# BatteryManagement.net
KiCad netlist of a schematic drawn in Altium Designer
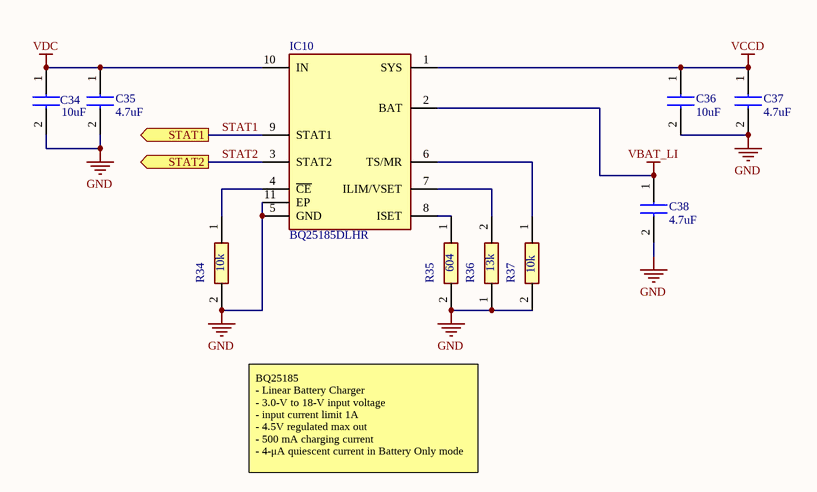
[diagram p0: BatteryManagement.SchDoc]

(export (version "E")
  (design (tool "Eeschema 10.0.6"))
  (components
    (comp (ref "C34")
      (value "10uF")
      (footprint "SamacSys:GRM18x")
      (description "Capacitor")
      (fields
        (field (name "MANUFACTURER_PART_NUMBER") "GRM188R61E106KA73D")
        (field (name "MOUSER PART NUMBER") "81-GRM188R61E106KA3D")
      )
      (libsource (lib "*") (part "GRM188R61E106KA73D"))
    )
    (comp (ref "C35")
      (value "4.7uF")
      (footprint "SamacSys:CAPC1608X90N")
      (description "Capacitor")
      (fields
        (field (name "MANUFACTURER_PART_NUMBER") "GRM188R61E475KE11J")
        (field (name "MOUSER PART NUMBER") "81-GRM188R61E475KE1J")
      )
      (libsource (lib "*") (part "GRM188R61E475KE11J"))
    )
    (comp (ref "C36")
      (value "10uF")
      (footprint "SamacSys:GRM18x")
      (description "Capacitor")
      (fields
        (field (name "MANUFACTURER_PART_NUMBER") "GRM188R61E106KA73D")
        (field (name "MOUSER PART NUMBER") "81-GRM188R61E106KA3D")
      )
      (libsource (lib "*") (part "GRM188R61E106KA73D"))
    )
    (comp (ref "C37")
      (value "4.7uF")
      (footprint "SamacSys:CAPC1608X90N")
      (description "Capacitor")
      (fields
        (field (name "MANUFACTURER_PART_NUMBER") "GRM188R61E475KE11J")
        (field (name "MOUSER PART NUMBER") "81-GRM188R61E475KE1J")
      )
      (libsource (lib "*") (part "GRM188R61E475KE11J"))
    )
    (comp (ref "C38")
      (value "4.7uF")
      (footprint "SamacSys:CAPC1608X90N")
      (description "Capacitor")
      (fields
        (field (name "MANUFACTURER_PART_NUMBER") "GRM188R61E475KE11J")
        (field (name "MOUSER PART NUMBER") "81-GRM188R61E475KE1J")
      )
      (libsource (lib "*") (part "GRM188R61E475KE11J"))
    )
    (comp (ref "IC10")
      (value "BQ25185DLHR")
      (footprint "SamacSys:SON40P220X200X80-11N")
      (description "Integrated Circuit")
      (fields (field (name "MOUSER PART NUMBER") "595-BQ25185DLHR"))
      (libsource (lib "SamacSys") (part "BQ25185DLHR"))
    )
    (comp (ref "R34")
      (value "10k")
      (footprint "SamacSys:RESC1005X35N")
      (description "Resistor")
      (fields
        (field (name "MANUFACTURER_PART_NUMBER") "RT0402FRE0710KL")
        (field (name "MOUSER PART NUMBER") "603-RT0402FRE0710KL")
      )
      (libsource (lib "SamacSys") (part "RT0402FRE0710KL"))
    )
    (comp (ref "R35")
      (value "604")
      (footprint "SamacSys:RESC1005X35N")
      (description "Resistor")
      (fields
        (field (name "MANUFACTURER_PART_NUMBER") "RT0402BRD07604RL")
        (field (name "MOUSER PART NUMBER") "603-RT0402BRD0713KL")
      )
      (libsource (lib "SamacSys") (part "RT0402BRD07604RL"))
    )
    (comp (ref "R36")
      (value "13k")
      (footprint "SamacSys:RESC1005X35N")
      (description "Resistor")
      (fields
        (field (name "MANUFACTURER_PART_NUMBER") "RT0402BRD0713KL")
        (field (name "MOUSER PART NUMBER") "603-RT0402BRD0713KL")
      )
      (libsource (lib "*") (part "RT0402BRD0713KL"))
    )
    (comp (ref "R37")
      (value "10k")
      (footprint "SamacSys:RESC1005X35N")
      (description "Resistor")
      (fields
        (field (name "MANUFACTURER_PART_NUMBER") "RT0402FRE0710KL")
        (field (name "MOUSER PART NUMBER") "603-RT0402FRE0710KL")
      )
      (libsource (lib "SamacSys") (part "RT0402FRE0710KL"))
    )
  )
  (nets
    (net (code "1") (name "/STAT1") (class "Default")
      (node (ref "IC10") (pin "9") (pinfunction "STAT1_9") (pintype "passive"))
    )
    (net (code "2") (name "/STAT2") (class "Default")
      (node (ref "IC10") (pin "3") (pinfunction "STAT2_3") (pintype "passive"))
    )
    (net (code "3") (name "GND") (class "Default")
      (node (ref "C34") (pin "2") (pinfunction "2_2") (pintype "passive"))
      (node (ref "C35") (pin "2") (pinfunction "2_2") (pintype "passive"))
      (node (ref "C36") (pin "2") (pinfunction "2_2") (pintype "passive"))
      (node (ref "C37") (pin "2") (pinfunction "2_2") (pintype "passive"))
      (node (ref "C38") (pin "2") (pinfunction "2_2") (pintype "passive"))
      (node (ref "IC10") (pin "11") (pinfunction "EP_11") (pintype "passive"))
      (node (ref "IC10") (pin "5") (pinfunction "GND_5") (pintype "passive"))
      (node (ref "R34") (pin "2") (pinfunction "2_2") (pintype "passive"))
      (node (ref "R35") (pin "2") (pinfunction "2_2") (pintype "passive"))
      (node (ref "R36") (pin "1") (pinfunction "1_1") (pintype "passive"))
      (node (ref "R37") (pin "2") (pinfunction "2_2") (pintype "passive"))
    )
    (net (code "4") (name "Net-(IC10-ILIM{slash}VSET)") (class "Default")
      (node (ref "IC10") (pin "7") (pinfunction "ILIM/VSET_7") (pintype "passive"))
      (node (ref "R36") (pin "2") (pinfunction "2_2") (pintype "passive"))
    )
    (net (code "5") (name "Net-(IC10-ISET)") (class "Default")
      (node (ref "IC10") (pin "8") (pinfunction "ISET_8") (pintype "passive"))
      (node (ref "R35") (pin "1") (pinfunction "1_1") (pintype "passive"))
    )
    (net (code "6") (name "Net-(IC10-TS{slash}MR)") (class "Default")
      (node (ref "IC10") (pin "6") (pinfunction "TS/MR_6") (pintype "passive"))
      (node (ref "R37") (pin "1") (pinfunction "1_1") (pintype "passive"))
    )
    (net (code "7") (name "Net-(IC10-~{CE})") (class "Default")
      (node (ref "IC10") (pin "4") (pinfunction "~{CE}_4") (pintype "passive"))
      (node (ref "R34") (pin "1") (pinfunction "1_1") (pintype "passive"))
    )
    (net (code "8") (name "VBAT_LI") (class "Default")
      (node (ref "C38") (pin "1") (pinfunction "1_1") (pintype "passive"))
      (node (ref "IC10") (pin "2") (pinfunction "BAT_2") (pintype "passive"))
    )
    (net (code "9") (name "VCCD") (class "Default")
      (node (ref "C36") (pin "1") (pinfunction "1_1") (pintype "passive"))
      (node (ref "C37") (pin "1") (pinfunction "1_1") (pintype "passive"))
      (node (ref "IC10") (pin "1") (pinfunction "SYS_1") (pintype "passive"))
    )
    (net (code "10") (name "VDC") (class "Default")
      (node (ref "C34") (pin "1") (pinfunction "1_1") (pintype "passive"))
      (node (ref "C35") (pin "1") (pinfunction "1_1") (pintype "passive"))
      (node (ref "IC10") (pin "10") (pinfunction "IN_10") (pintype "passive"))
    )
  )
)
